# Power_Input_FET.net
KiCad netlist of a schematic drawn in Altium Designer
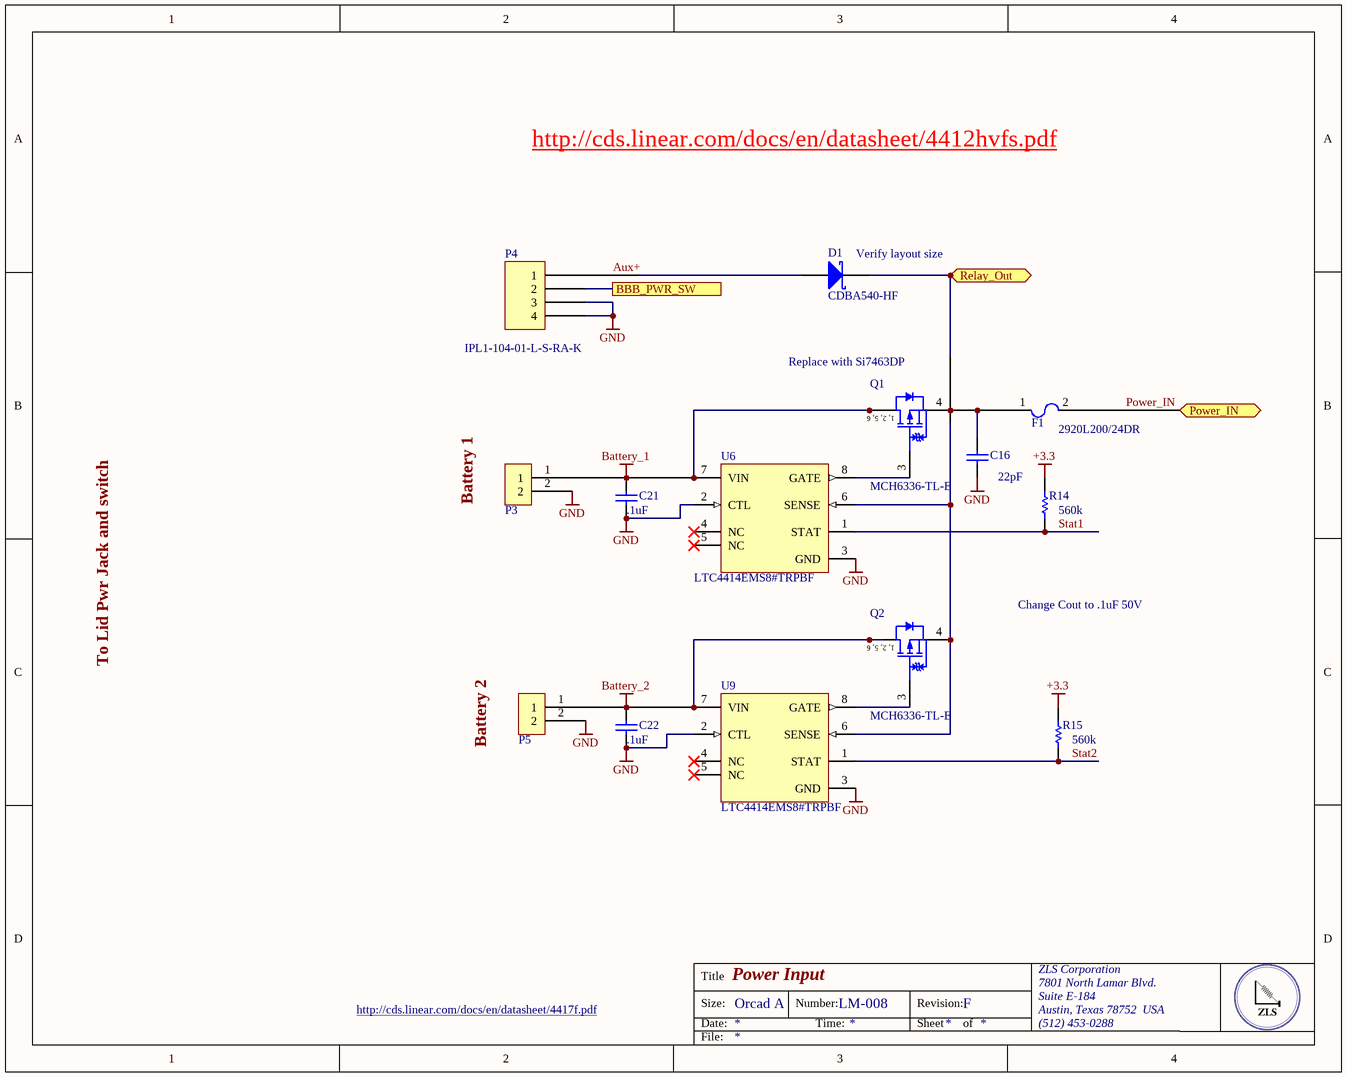
[diagram p0: Power_Input_FET.SchDoc]

(export (version "E")
  (design (tool "Eeschema 10.0.6"))
  (components
    (comp (ref "C16")
      (value "CAP CER 10UF 6.3V X5R 1206")
      (footprint "CAPC1206(3216)130_N")
      (fields
        (field (name "MANUFACTURER") "Taiyo Yuden")
        (field (name "MANUFACTURER PART NUMBER") "JMK316BJ106ML-T")
        (field (name "TOLERANCE") "±20%")
        (field (name "CAPACITANCE") "22pF")
      )
      (libsource (lib "Altium Content Vault") (part "CMP-1037-04913-1"))
    )
    (comp (ref "C21")
      (value "CAP CER 10UF 6.3V X5R 1206")
      (footprint "CAPC1206(3216)130_N")
      (fields
        (field (name "MANUFACTURER") "Taiyo Yuden")
        (field (name "MANUFACTURER PART NUMBER") "JMK316BJ106ML-T")
        (field (name "TOLERANCE") "±20%")
        (field (name "CAPACITANCE") ".1uF")
      )
      (libsource (lib "Altium Content Vault") (part "CMP-1037-04913-1"))
    )
    (comp (ref "C22")
      (value "CAP CER 10UF 6.3V X5R 1206")
      (footprint "CAPC1206(3216)130_N")
      (fields
        (field (name "MANUFACTURER") "Taiyo Yuden")
        (field (name "MANUFACTURER PART NUMBER") "JMK316BJ106ML-T")
        (field (name "TOLERANCE") "±20%")
        (field (name "CAPACITANCE") ".1uF")
      )
      (libsource (lib "Altium Content Vault") (part "CMP-1037-04913-1"))
    )
    (comp (ref "D1")
      (value "CDBA540-HF")
      (footprint "VISH-DO-214AC-2_M")
      (description "DIODE SCHOTTKY 40V 5A DO214AB")
      (fields (field (name "MANUFACTURER") "Comchip Technology"))
      (libsource (lib "Miscellaneous Devices") (part "D Schottky"))
    )
    (comp (ref "F1")
      (value "PCT")
      (footprint "CAPC7451X12N")
      (libsource (lib "ZLS_Schematic_lib") (part "PCT"))
    )
    (comp (ref "P3")
      (value "IPL1-102-01-F-S-RA-K")
      (footprint "IPL1-102-01-F-S-RA-K")
      (libsource (lib "ZLS_Schematic_lib") (part "IPL1-102-01-F-S-RA-K"))
    )
    (comp (ref "P4")
      (value "IPL1-104-01-L-S-RA-K")
      (footprint "IPL1-104-01-L-S-RA-K")
      (fields
        (field (name "MANUFACTURER") "Samtec Inc.")
        (field (name "MANUFACTURER PART NUMBER") "IPL1-104-01-L-S-RA-K")
      )
      (libsource (lib "ZLS_Schematic_lib") (part "IPL1-104-01-L-S-RA-K"))
    )
    (comp (ref "P5")
      (value "IPL1-102-01-F-S-RA-K")
      (footprint "IPL1-102-01-F-S-RA-K")
      (libsource (lib "ZLS_Schematic_lib") (part "IPL1-102-01-F-S-RA-K"))
    )
    (comp (ref "Q1")
      (value "MCH6336-TL-E")
      (footprint "ONSC-MCPH-6_V")
      (description "P-Channel Power MOSFET, -12 V, -5 A, 43 mOhm, Single, 6-Pin MCPH, Pb-Free, Tape and Reel")
      (fields (field (name "MANUFACTURER") "On Semiconductor"))
      (libsource (lib "Altium Content Vault") (part "ONSC-PMOS-6_B"))
    )
    (comp (ref "Q2")
      (value "MCH6336-TL-E")
      (footprint "ONSC-MCPH-6_V")
      (description "P-Channel Power MOSFET, -12 V, -5 A, 43 mOhm, Single, 6-Pin MCPH, Pb-Free, Tape and Reel")
      (fields (field (name "MANUFACTURER") "On Semiconductor"))
      (libsource (lib "Altium Content Vault") (part "ONSC-PMOS-6_B"))
    )
    (comp (ref "R14")
      (value "560k")
      (footprint "RESC0402(1005)_L")
      (fields (field (name "TOLERANCE") "±1%"))
      (libsource (lib "Altium Content Vault") (part "CMP-1011-00927-1"))
    )
    (comp (ref "R15")
      (value "560k")
      (footprint "RESC0402(1005)_L")
      (fields (field (name "TOLERANCE") "±1%"))
      (libsource (lib "Altium Content Vault") (part "CMP-1011-00927-1"))
    )
    (comp (ref "U6")
      (value "LTC4414EMS8#TRPBF")
      (footprint "LT-MS8-8_L")
      (fields (field (name "MANUFACTURER") "Linear Technology"))
      (libsource (lib "Altium Content Vault") (part "CMP-0479-00214-1"))
    )
    (comp (ref "U9")
      (value "LTC4414EMS8#TRPBF")
      (footprint "LT-MS8-8_L")
      (fields (field (name "MANUFACTURER") "Linear Technology"))
      (libsource (lib "Altium Content Vault") (part "CMP-0479-00214-1"))
    )
  )
  (nets
    (net (code "1") (name "+3.3") (class "Default")
      (node (ref "R14") (pin "2") (pinfunction "2_2") (pintype "passive"))
      (node (ref "R15") (pin "2") (pinfunction "2_2") (pintype "passive"))
    )
    (net (code "2") (name "/Aux+") (class "Default")
      (node (ref "D1") (pin "1") (pinfunction "A_1") (pintype "passive"))
      (node (ref "P4") (pin "1") (pinfunction "1_1") (pintype "passive"))
    )
    (net (code "3") (name "/BBB_PWR_SW") (class "Default")
      (node (ref "P4") (pin "2") (pinfunction "2_2") (pintype "passive"))
    )
    (net (code "4") (name "/Power_IN") (class "Default")
      (node (ref "F1") (pin "2") (pinfunction "2_2") (pintype "passive"))
    )
    (net (code "5") (name "/Relay_Out") (class "Default")
      (node (ref "C16") (pin "2") (pinfunction "2_2") (pintype "passive"))
      (node (ref "D1") (pin "2") (pinfunction "K_2") (pintype "passive"))
      (node (ref "F1") (pin "1") (pinfunction "1_1") (pintype "passive"))
      (node (ref "Q1") (pin "4") (pinfunction "S_4") (pintype "passive"))
      (node (ref "Q2") (pin "4") (pinfunction "S_4") (pintype "passive"))
      (node (ref "U6") (pin "6") (pinfunction "SENSE_6") (pintype "input"))
      (node (ref "U9") (pin "6") (pinfunction "SENSE_6") (pintype "input"))
    )
    (net (code "6") (name "/Stat1") (class "Default")
      (node (ref "R14") (pin "1") (pinfunction "1_1") (pintype "passive"))
      (node (ref "U6") (pin "1") (pinfunction "STAT_1") (pintype "open_collector"))
    )
    (net (code "7") (name "/Stat2") (class "Default")
      (node (ref "R15") (pin "1") (pinfunction "1_1") (pintype "passive"))
      (node (ref "U9") (pin "1") (pinfunction "STAT_1") (pintype "open_collector"))
    )
    (net (code "8") (name "Battery_1") (class "Default")
      (node (ref "C21") (pin "2") (pinfunction "2_2") (pintype "passive"))
      (node (ref "P3") (pin "1") (pinfunction "1_1") (pintype "passive"))
      (node (ref "Q1") (pin "1") (pinfunction "D_1") (pintype "passive"))
      (node (ref "Q1") (pin "2") (pinfunction "D_2") (pintype "passive"))
      (node (ref "Q1") (pin "5") (pinfunction "D_5") (pintype "passive"))
      (node (ref "Q1") (pin "6") (pinfunction "D_6") (pintype "passive"))
      (node (ref "U6") (pin "7") (pinfunction "VIN_7") (pintype "power_in"))
    )
    (net (code "9") (name "Battery_2") (class "Default")
      (node (ref "C22") (pin "2") (pinfunction "2_2") (pintype "passive"))
      (node (ref "P5") (pin "1") (pinfunction "1_1") (pintype "passive"))
      (node (ref "Q2") (pin "1") (pinfunction "D_1") (pintype "passive"))
      (node (ref "Q2") (pin "2") (pinfunction "D_2") (pintype "passive"))
      (node (ref "Q2") (pin "5") (pinfunction "D_5") (pintype "passive"))
      (node (ref "Q2") (pin "6") (pinfunction "D_6") (pintype "passive"))
      (node (ref "U9") (pin "7") (pinfunction "VIN_7") (pintype "power_in"))
    )
    (net (code "10") (name "GND") (class "Default")
      (node (ref "C16") (pin "1") (pinfunction "1_1") (pintype "passive"))
      (node (ref "C21") (pin "1") (pinfunction "1_1") (pintype "passive"))
      (node (ref "C22") (pin "1") (pinfunction "1_1") (pintype "passive"))
      (node (ref "P3") (pin "2") (pinfunction "2_2") (pintype "passive"))
      (node (ref "P4") (pin "3") (pinfunction "3_3") (pintype "passive"))
      (node (ref "P4") (pin "4") (pinfunction "4_4") (pintype "passive"))
      (node (ref "P5") (pin "2") (pinfunction "2_2") (pintype "passive"))
      (node (ref "U6") (pin "2") (pinfunction "CTL_2") (pintype "input"))
      (node (ref "U6") (pin "3") (pinfunction "GND_3") (pintype "power_in"))
      (node (ref "U9") (pin "2") (pinfunction "CTL_2") (pintype "input"))
      (node (ref "U9") (pin "3") (pinfunction "GND_3") (pintype "power_in"))
    )
    (net (code "11") (name "Net-(Q1-G)") (class "Default")
      (node (ref "Q1") (pin "3") (pinfunction "G_3") (pintype "passive"))
      (node (ref "U6") (pin "8") (pinfunction "GATE_8") (pintype "output"))
    )
    (net (code "12") (name "Net-(Q2-G)") (class "Default")
      (node (ref "Q2") (pin "3") (pinfunction "G_3") (pintype "passive"))
      (node (ref "U9") (pin "8") (pinfunction "GATE_8") (pintype "output"))
    )
    (net (code "13") (name "unconnected-(U6-NC-Pad4)") (class "Default")
      (node (ref "U6") (pin "4") (pinfunction "NC_4") (pintype "passive+no_connect"))
    )
    (net (code "14") (name "unconnected-(U6-NC-Pad5)") (class "Default")
      (node (ref "U6") (pin "5") (pinfunction "NC_5") (pintype "passive+no_connect"))
    )
    (net (code "15") (name "unconnected-(U9-NC-Pad4)") (class "Default")
      (node (ref "U9") (pin "4") (pinfunction "NC_4") (pintype "passive+no_connect"))
    )
    (net (code "16") (name "unconnected-(U9-NC-Pad5)") (class "Default")
      (node (ref "U9") (pin "5") (pinfunction "NC_5") (pintype "passive+no_connect"))
    )
  )
)
